# POWER_SUPPLY.net
KiCad netlist of a schematic drawn in Altium Designer
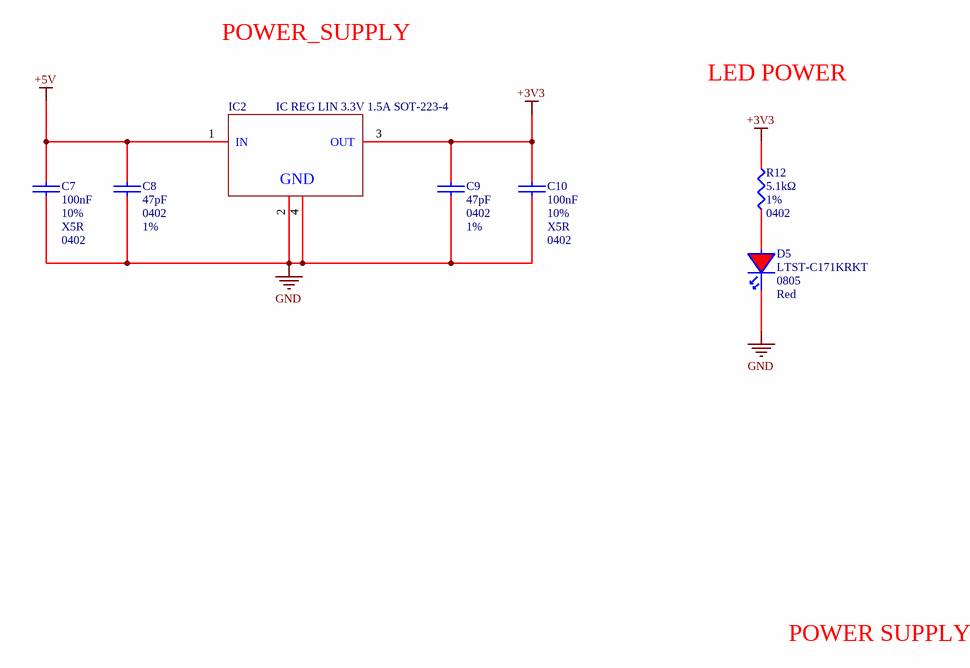
[diagram p0: POWER_SUPPLY.SchDoc]

(export (version "E")
  (design (tool "Eeschema 10.0.6"))
  (components
    (comp (ref "C7")
      (value "100nF")
      (footprint "C0402")
      (description "50V 100nF X5R ±10% 0402 Multilayer Ceramic Capacitors MLCC - SMD/SMT ROHS")
      (fields
        (field (name "MANUFACTURER") "Yageo Group")
        (field (name "MANUFACTURER PART NUMBER") "CC0402KRX5R9BB104")
        (field (name "TOLERANCE") "10%")
        (field (name "DIELECTRIC") "X5R")
        (field (name "CASE/PACKAGE") "0402")
      )
      (libsource (lib "Schlib") (part "CC0402KRX5R9BB104"))
    )
    (comp (ref "C8")
      (value "47pF")
      (footprint "C0402")
      (description "50V 47pF NP0 ±1% 0402 Multilayer Ceramic Capacitors MLCC - SMD/SMT ROHS")
      (fields
        (field (name "MANUFACTURER") "Yageo Group")
        (field (name "MANUFACTURER PART NUMBER") "CC0402FRNPO9BN470")
        (field (name "CASE/PACKAGE") "0402")
        (field (name "TOLERANCE") "1%")
      )
      (libsource (lib "Schlib") (part "CC0402FRNPO9BN470"))
    )
    (comp (ref "C9")
      (value "47pF")
      (footprint "C0402")
      (description "50V 47pF NP0 ±1% 0402 Multilayer Ceramic Capacitors MLCC - SMD/SMT ROHS")
      (fields
        (field (name "MANUFACTURER") "Yageo Group")
        (field (name "MANUFACTURER PART NUMBER") "CC0402FRNPO9BN470")
        (field (name "CASE/PACKAGE") "0402")
        (field (name "TOLERANCE") "1%")
      )
      (libsource (lib "Schlib") (part "CC0402FRNPO9BN470"))
    )
    (comp (ref "C10")
      (value "100nF")
      (footprint "C0402")
      (description "50V 100nF X5R ±10% 0402 Multilayer Ceramic Capacitors MLCC - SMD/SMT ROHS")
      (fields
        (field (name "MANUFACTURER") "Yageo Group")
        (field (name "MANUFACTURER PART NUMBER") "CC0402KRX5R9BB104")
        (field (name "TOLERANCE") "10%")
        (field (name "DIELECTRIC") "X5R")
        (field (name "CASE/PACKAGE") "0402")
      )
      (libsource (lib "Schlib") (part "CC0402KRX5R9BB104"))
    )
    (comp (ref "D5")
      (value "LTST-C171KRKT")
      (footprint "LED_LTST-C171_LTO-L")
      (description "LED red 0805 wavelength 631nm light intensity 54mcd Front Mounting")
      (fields
        (field (name "MANUFACTURER") "Diodes Inc.")
        (field (name "LCSC PART") "C284871")
        (field (name "CASE CODE (IMPERIAL)") "0805")
        (field (name "COLOR") "Red")
      )
      (libsource (lib "Schlib") (part "LTST-C171KRKT"))
    )
    (comp (ref "IC2")
      (value "IC REG LIN 3.3V 1.5A SOT-223-4")
      (footprint "DCY4_TEX-L")
      (description "1.5-A, 20-V, low-dropout voltage regulator with reverse current & reverse voltage protection")
      (fields
        (field (name "MANUFACTURER") "Texas Instruments")
        (field (name "MANUFACTURER PART NUMBER") "TL1963A-33DCYR")
      )
      (libsource (lib "Schlib") (part "TL1963A-33DCYR"))
    )
    (comp (ref "R12")
      (value "5.1kΩ")
      (footprint "R0402")
      (description "62.5mW Thick Film Resistors 50V ±100ppm/℃ ±1% 5.1kΩ 0402 Chip Resistor - Surface Mount ROHS")
      (fields
        (field (name "MANUFACTURER") "Yageo Group")
        (field (name "MANUFACTURER PART NUMBER") "RC0402FR-075K1L")
        (field (name "TOLERANCE") "1%")
        (field (name "CASE/PACKAGE") "0402")
      )
      (libsource (lib "Schlib") (part "RC0402FR-075K1L"))
    )
  )
  (nets
    (net (code "1") (name "+3V3") (class "Default")
      (node (ref "C10") (pin "2") (pinfunction "2_2") (pintype "passive"))
      (node (ref "C9") (pin "2") (pinfunction "2_2") (pintype "passive"))
      (node (ref "IC2") (pin "3") (pinfunction "OUT_3") (pintype "passive"))
      (node (ref "R12") (pin "2") (pinfunction "2_2") (pintype "passive"))
    )
    (net (code "2") (name "+5V") (class "Default")
      (node (ref "C7") (pin "2") (pinfunction "2_2") (pintype "passive"))
      (node (ref "C8") (pin "2") (pinfunction "2_2") (pintype "passive"))
      (node (ref "IC2") (pin "1") (pinfunction "IN_1") (pintype "passive"))
    )
    (net (code "3") (name "GND") (class "Default")
      (node (ref "C10") (pin "1") (pinfunction "1_1") (pintype "passive"))
      (node (ref "C7") (pin "1") (pinfunction "1_1") (pintype "passive"))
      (node (ref "C8") (pin "1") (pinfunction "1_1") (pintype "passive"))
      (node (ref "C9") (pin "1") (pinfunction "1_1") (pintype "passive"))
      (node (ref "D5") (pin "1") (pinfunction "1_1") (pintype "passive"))
      (node (ref "IC2") (pin "2") (pinfunction "GND_2") (pintype "passive"))
      (node (ref "IC2") (pin "4") (pinfunction "GND_4") (pintype "passive"))
    )
    (net (code "4") (name "Net-(D5-Pad2)") (class "Default")
      (node (ref "D5") (pin "2") (pinfunction "2_2") (pintype "passive"))
      (node (ref "R12") (pin "1") (pinfunction "1_1") (pintype "passive"))
    )
  )
)
